# schematic.net
KiCad netlist of a schematic drawn in EasyEDA
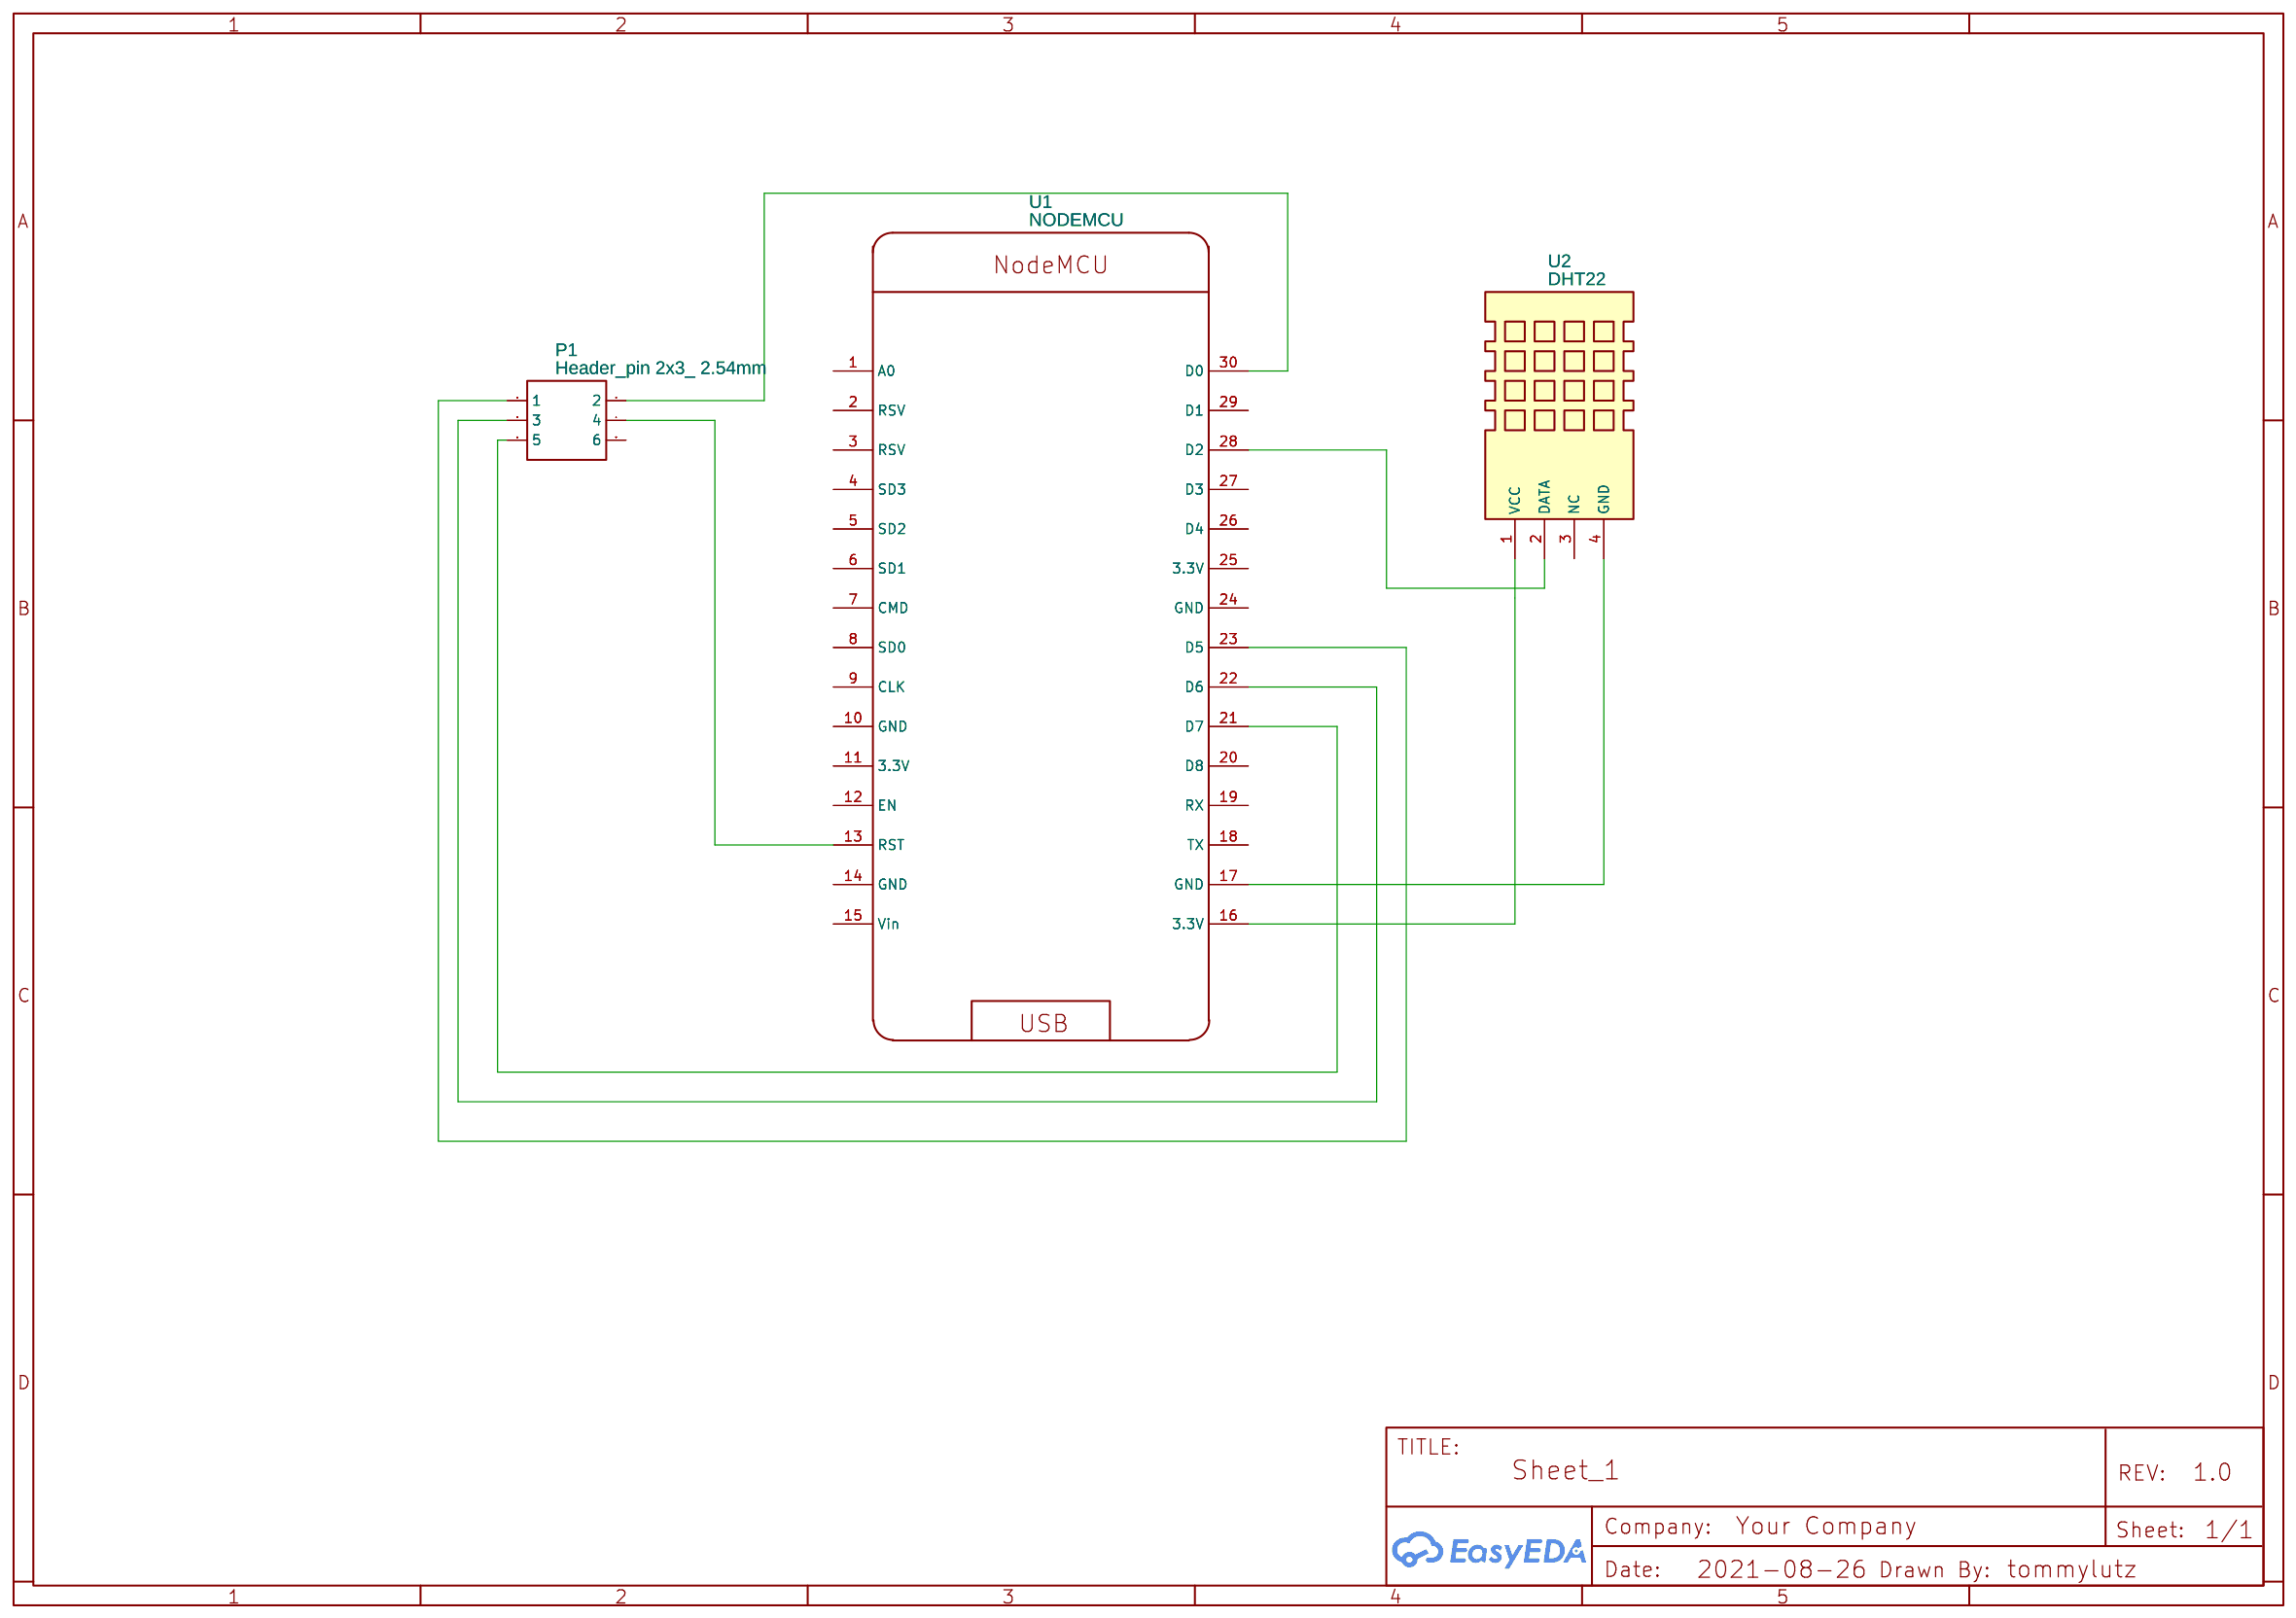
[diagram p0: schematic sheet]

(export (version "E")
  (design (tool "Eeschema 10.0.6"))
  (components
    (comp (ref "P1")
      (value "Header_pin 2x3_ 2.54mm")
      (fields
        (field (name "BOM_Manufacturer Part") "Double Rows2.54mm2*2pHeaders  Pins")
        (field (name "BOM_Supplier Part") "C66690")
      )
      (libsource (lib "") (part "Header_pin 2x3_ 2.54mm"))
    )
    (comp (ref "U1") (value "NODEMCU") (libsource (lib "") (part "NODEMCU")))
    (comp (ref "U2")
      (value "DHT22")
      (fields (field (name "BOM_Supplier Part") "PRODUCT ID: 385"))
      (libsource (lib "") (part "DHT22"))
    )
  )
  (nets
    (net (code "1") (name "Net-(U1-D0)") (class "Default")
      (node (ref "P1") (pin "2") (pinfunction "2_2") (pintype "input"))
      (node (ref "U1") (pin "30") (pinfunction "D0_30") (pintype "unspecified"))
    )
    (net (code "2") (name "Net-(U1-D2)") (class "Default")
      (node (ref "U1") (pin "28") (pinfunction "D2_28") (pintype "unspecified"))
      (node (ref "U2") (pin "2") (pinfunction "DATA_2") (pintype "unspecified"))
    )
    (net (code "3") (name "Net-(U1-D5)") (class "Default")
      (node (ref "P1") (pin "1") (pinfunction "1_1") (pintype "input"))
      (node (ref "U1") (pin "23") (pinfunction "D5_23") (pintype "unspecified"))
    )
    (net (code "4") (name "Net-(U1-D6)") (class "Default")
      (node (ref "P1") (pin "3") (pinfunction "3_3") (pintype "input"))
      (node (ref "U1") (pin "22") (pinfunction "D6_22") (pintype "unspecified"))
    )
    (net (code "5") (name "Net-(U1-D7)") (class "Default")
      (node (ref "P1") (pin "5") (pinfunction "5_5") (pintype "input"))
      (node (ref "U1") (pin "21") (pinfunction "D7_21") (pintype "unspecified"))
    )
    (net (code "6") (name "Net-(U1-RST)") (class "Default")
      (node (ref "P1") (pin "4") (pinfunction "4_4") (pintype "input"))
      (node (ref "U1") (pin "13") (pinfunction "RST_13") (pintype "unspecified"))
    )
    (net (code "7") (name "Net-(U2-GND)") (class "Default")
      (node (ref "U1") (pin "17") (pinfunction "GND_17") (pintype "unspecified"))
      (node (ref "U2") (pin "4") (pinfunction "GND_4") (pintype "unspecified"))
    )
    (net (code "8") (name "Net-(U2-VCC)") (class "Default")
      (node (ref "U1") (pin "16") (pinfunction "3.3V_16") (pintype "unspecified"))
      (node (ref "U2") (pin "1") (pinfunction "VCC_1") (pintype "unspecified"))
    )
    (net (code "9") (name "unconnected-(P1-Pad6)") (class "Default")
      (node (ref "P1") (pin "6") (pinfunction "6_6") (pintype "input"))
    )
    (net (code "10") (name "unconnected-(U1-3.3V-Pad11)") (class "Default")
      (node (ref "U1") (pin "11") (pinfunction "3.3V_11") (pintype "unspecified"))
    )
    (net (code "11") (name "unconnected-(U1-3.3V-Pad25)") (class "Default")
      (node (ref "U1") (pin "25") (pinfunction "3.3V_25") (pintype "unspecified"))
    )
    (net (code "12") (name "unconnected-(U1-A0-Pad1)") (class "Default")
      (node (ref "U1") (pin "1") (pinfunction "A0_1") (pintype "unspecified"))
    )
    (net (code "13") (name "unconnected-(U1-CLK-Pad9)") (class "Default")
      (node (ref "U1") (pin "9") (pinfunction "CLK_9") (pintype "unspecified"))
    )
    (net (code "14") (name "unconnected-(U1-CMD-Pad7)") (class "Default")
      (node (ref "U1") (pin "7") (pinfunction "CMD_7") (pintype "unspecified"))
    )
    (net (code "15") (name "unconnected-(U1-D1-Pad29)") (class "Default")
      (node (ref "U1") (pin "29") (pinfunction "D1_29") (pintype "unspecified"))
    )
    (net (code "16") (name "unconnected-(U1-D3-Pad27)") (class "Default")
      (node (ref "U1") (pin "27") (pinfunction "D3_27") (pintype "unspecified"))
    )
    (net (code "17") (name "unconnected-(U1-D4-Pad26)") (class "Default")
      (node (ref "U1") (pin "26") (pinfunction "D4_26") (pintype "unspecified"))
    )
    (net (code "18") (name "unconnected-(U1-D8-Pad20)") (class "Default")
      (node (ref "U1") (pin "20") (pinfunction "D8_20") (pintype "unspecified"))
    )
    (net (code "19") (name "unconnected-(U1-EN-Pad12)") (class "Default")
      (node (ref "U1") (pin "12") (pinfunction "EN_12") (pintype "unspecified"))
    )
    (net (code "20") (name "unconnected-(U1-GND-Pad10)") (class "Default")
      (node (ref "U1") (pin "10") (pinfunction "GND_10") (pintype "unspecified"))
    )
    (net (code "21") (name "unconnected-(U1-GND-Pad14)") (class "Default")
      (node (ref "U1") (pin "14") (pinfunction "GND_14") (pintype "unspecified"))
    )
    (net (code "22") (name "unconnected-(U1-GND-Pad24)") (class "Default")
      (node (ref "U1") (pin "24") (pinfunction "GND_24") (pintype "unspecified"))
    )
    (net (code "23") (name "unconnected-(U1-RSV-Pad2)") (class "Default")
      (node (ref "U1") (pin "2") (pinfunction "RSV_2") (pintype "unspecified"))
    )
    (net (code "24") (name "unconnected-(U1-RSV-Pad3)") (class "Default")
      (node (ref "U1") (pin "3") (pinfunction "RSV_3") (pintype "unspecified"))
    )
    (net (code "25") (name "unconnected-(U1-RX-Pad19)") (class "Default")
      (node (ref "U1") (pin "19") (pinfunction "RX_19") (pintype "unspecified"))
    )
    (net (code "26") (name "unconnected-(U1-SD0-Pad8)") (class "Default")
      (node (ref "U1") (pin "8") (pinfunction "SD0_8") (pintype "unspecified"))
    )
    (net (code "27") (name "unconnected-(U1-SD1-Pad6)") (class "Default")
      (node (ref "U1") (pin "6") (pinfunction "SD1_6") (pintype "unspecified"))
    )
    (net (code "28") (name "unconnected-(U1-SD2-Pad5)") (class "Default")
      (node (ref "U1") (pin "5") (pinfunction "SD2_5") (pintype "unspecified"))
    )
    (net (code "29") (name "unconnected-(U1-SD3-Pad4)") (class "Default")
      (node (ref "U1") (pin "4") (pinfunction "SD3_4") (pintype "unspecified"))
    )
    (net (code "30") (name "unconnected-(U1-TX-Pad18)") (class "Default")
      (node (ref "U1") (pin "18") (pinfunction "TX_18") (pintype "unspecified"))
    )
    (net (code "31") (name "unconnected-(U1-Vin-Pad15)") (class "Default")
      (node (ref "U1") (pin "15") (pinfunction "Vin_15") (pintype "unspecified"))
    )
    (net (code "32") (name "unconnected-(U2-NC-Pad3)") (class "Default")
      (node (ref "U2") (pin "3") (pinfunction "NC_3") (pintype "unspecified"))
    )
  )
)
